# Serial_to_USB_Converter.net
KiCad netlist of a schematic drawn in Altium Designer
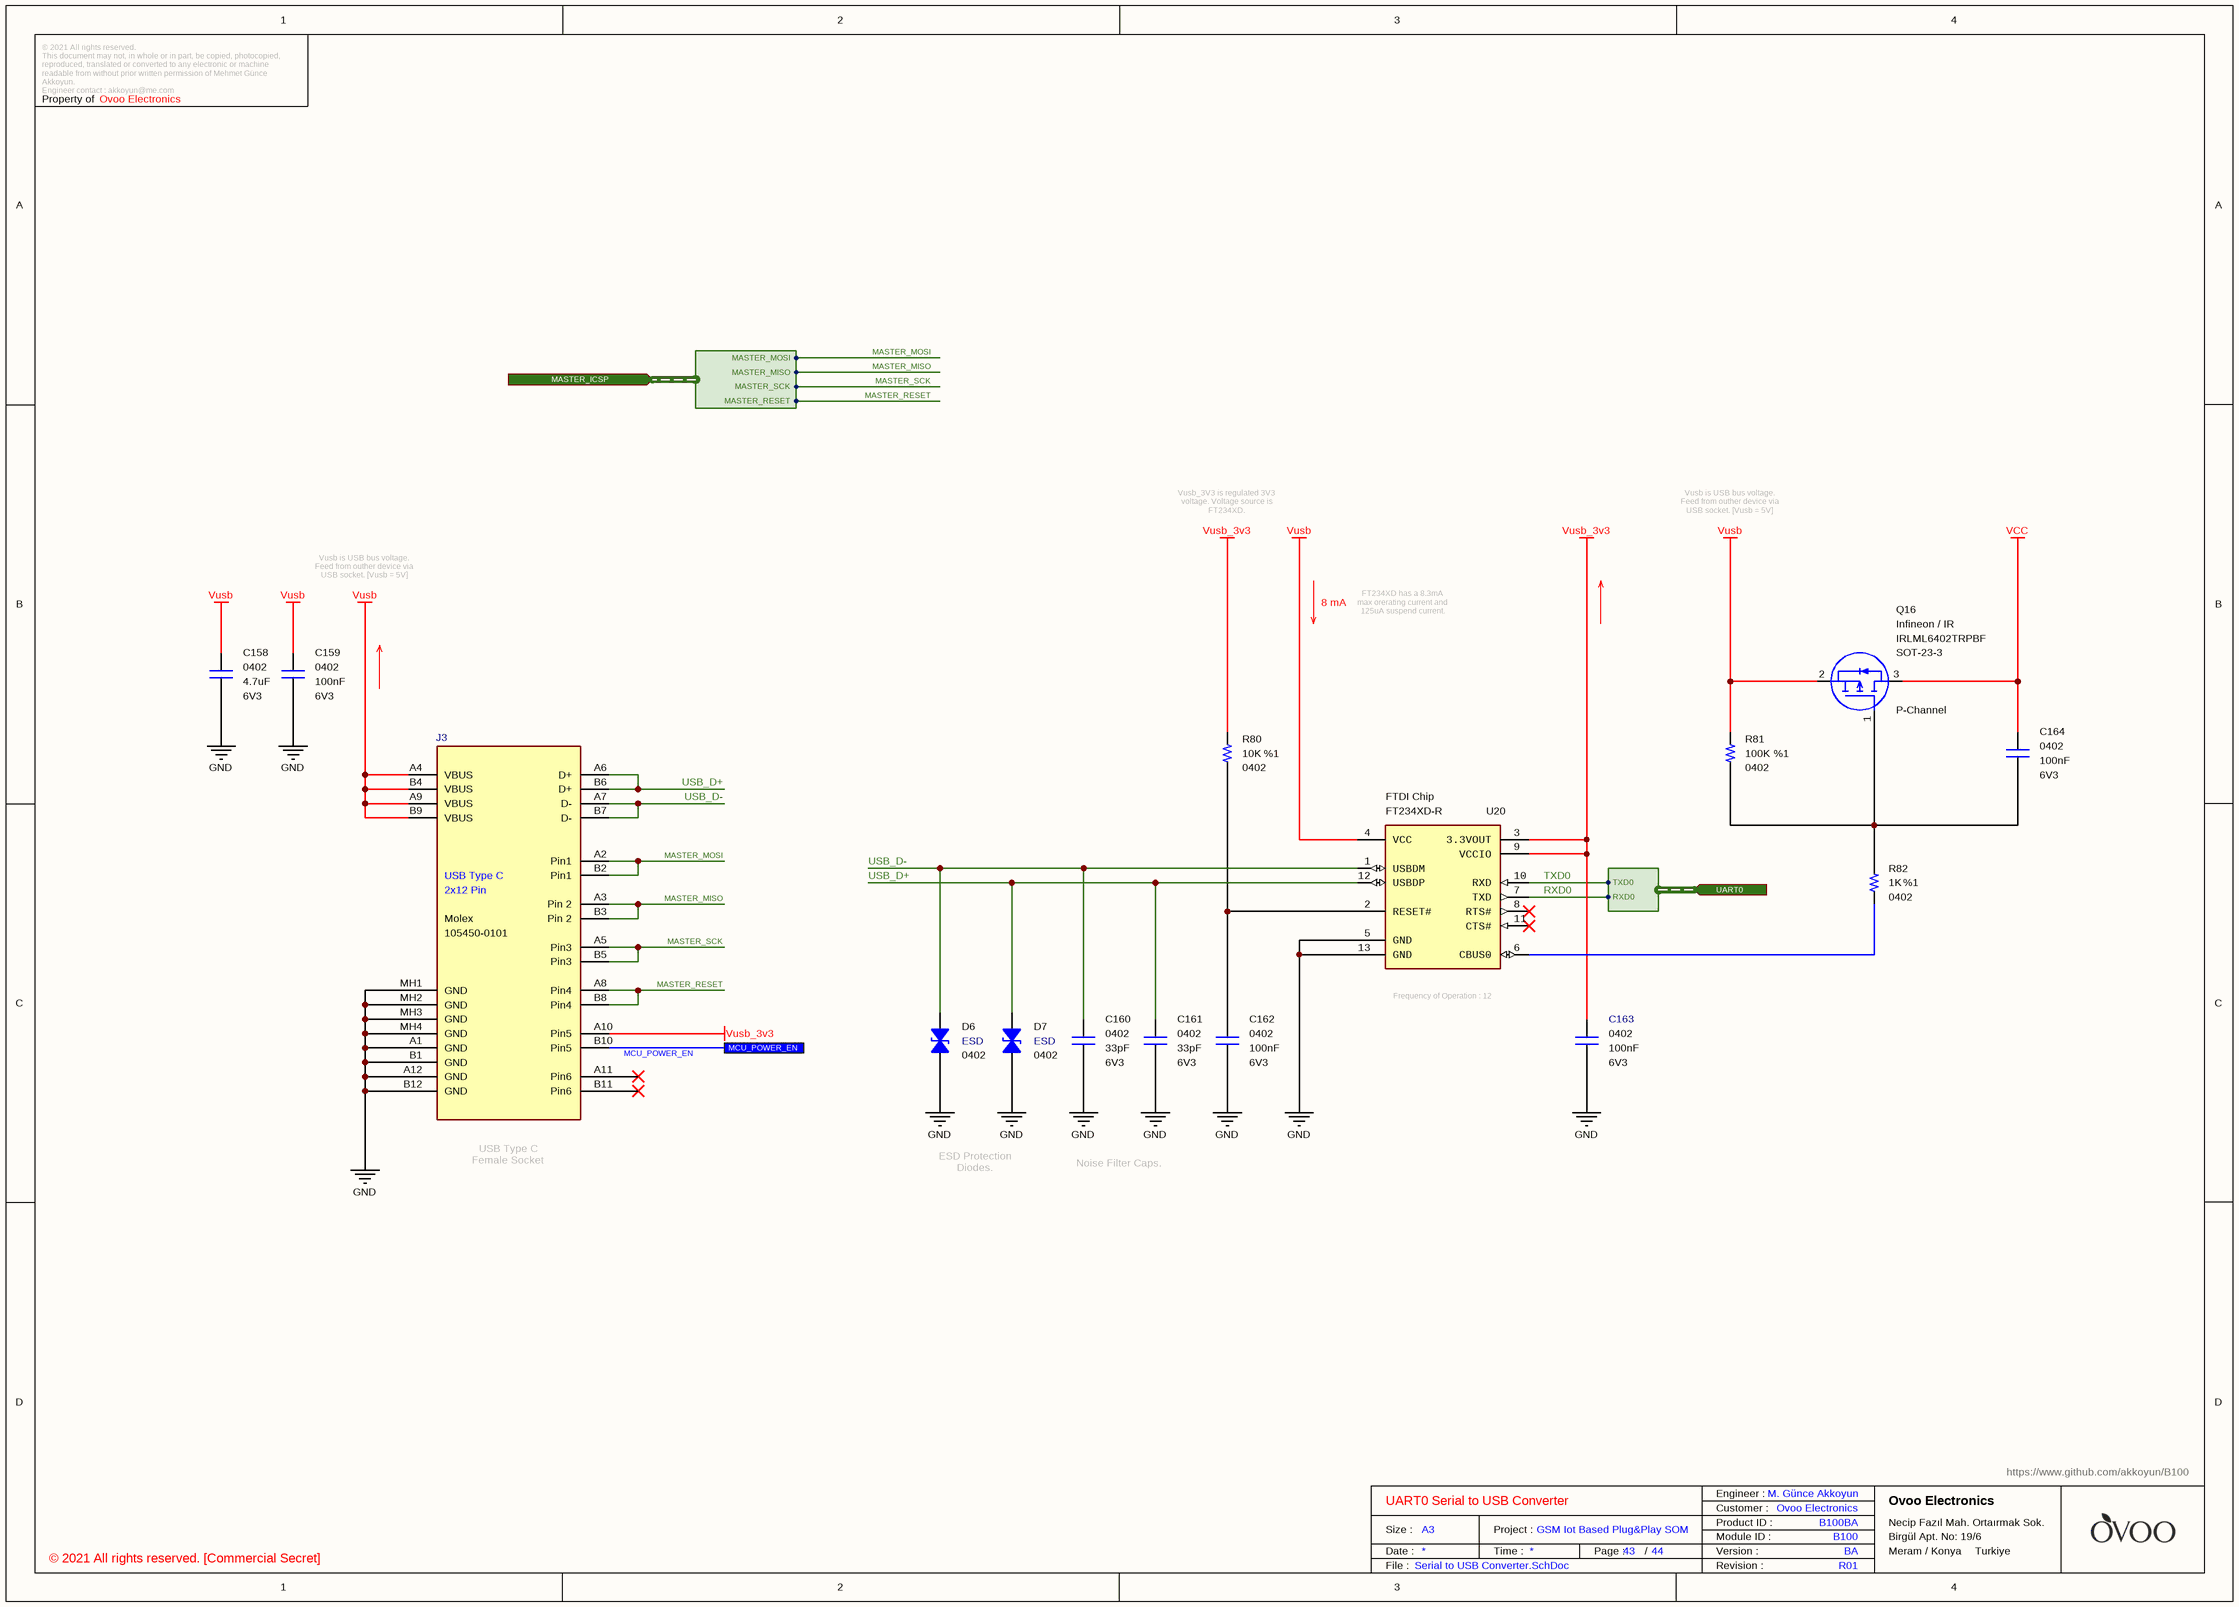
[diagram p0: Serial to USB Converter.SchDoc]

(export (version "E")
  (design (tool "Eeschema 10.0.6"))
  (components
    (comp (ref "C158")
      (value "4.7uF")
      (footprint "CAPACITOR_0402")
      (description "Capacitor - 4.7uF [0402] (Ceramic)")
      (fields
        (field (name "TOLERANCE") "%20")
        (field (name "CASE") "0402")
        (field (name "VOLTAGE") "6V3")
        (field (name "MANUFACTURER PART NUMBER") "C0402C475M9PACTU")
      )
      (libsource (lib "Ovoo_Library") (part "Capacitor - 4.7uF [0402-6V3]"))
    )
    (comp (ref "C159")
      (value "100nF")
      (footprint "CAPACITOR_0402")
      (description "Capacitor - 100nF [0402-6V3] (Ceramic)")
      (fields
        (field (name "TOLERANCE") "%10")
        (field (name "CASE") "0402")
        (field (name "VOLTAGE") "6V3")
        (field (name "MANUFACTURER PART NUMBER") "04026D104KAT4A")
      )
      (libsource (lib "Ovoo_Library") (part "Capacitor - 100nF [0402-6V3]"))
    )
    (comp (ref "C160")
      (value "33pF")
      (footprint "CAPACITOR_0402")
      (description "Capacitor - 33pF [0402] (Ceramic)")
      (fields
        (field (name "TOLERANCE") "10%")
        (field (name "CASE") "0402")
        (field (name "VOLTAGE") "6V3")
        (field (name "MANUFACTURER PART NUMBER") "C0402C330J9RACAUTO")
      )
      (libsource (lib "Ovoo_Library") (part "Capacitor - 33pF [0402-6V3]"))
    )
    (comp (ref "C161")
      (value "33pF")
      (footprint "CAPACITOR_0402")
      (description "Capacitor - 33pF [0402] (Ceramic)")
      (fields
        (field (name "TOLERANCE") "10%")
        (field (name "CASE") "0402")
        (field (name "VOLTAGE") "6V3")
        (field (name "MANUFACTURER PART NUMBER") "C0402C330J9RACAUTO")
      )
      (libsource (lib "Ovoo_Library") (part "Capacitor - 33pF [0402-6V3]"))
    )
    (comp (ref "C162")
      (value "100nF")
      (footprint "CAPACITOR_0402")
      (description "Capacitor - 100nF [0402-6V3] (Ceramic)")
      (fields
        (field (name "CASE") "0402")
        (field (name "TOLERANCE") "%10")
        (field (name "VOLTAGE") "6V3")
        (field (name "MANUFACTURER PART NUMBER") "04026D104KAT4A")
      )
      (libsource (lib "Ovoo_Library") (part "Capacitor - 100nF [0402-6V3]"))
    )
    (comp (ref "C163")
      (value "100nF")
      (footprint "CAPACITOR_0402")
      (description "Capacitor - 100nF [0402-6V3] (Ceramic)")
      (fields
        (field (name "CASE") "0402")
        (field (name "TOLERANCE") "%10")
        (field (name "VOLTAGE") "6V3")
        (field (name "MANUFACTURER PART NUMBER") "04026D104KAT4A")
      )
      (libsource (lib "Ovoo_Library") (part "Capacitor - 100nF [0402-6V3]"))
    )
    (comp (ref "C164")
      (value "100nF")
      (footprint "CAPACITOR_0402")
      (description "Capacitor - 100nF [0402-6V3] (Ceramic)")
      (fields
        (field (name "TOLERANCE") "%10")
        (field (name "CASE") "0402")
        (field (name "VOLTAGE") "6V3")
        (field (name "MANUFACTURER PART NUMBER") "04026D104KAT4A")
      )
      (libsource (lib "Ovoo_Library") (part "Capacitor - 100nF [0402-6V3]"))
    )
    (comp (ref "D6")
      (value "ESD Suppressors")
      (footprint "ESD_0402")
      (description "TVS Diode (Bi-directional)")
      (fields
        (field (name "CASE") "0402")
        (field (name "MANUFACTURER PART NUMBER") "0402ESDA-MLP1")
        (field (name "MOUSER PART NUMBER") "504-0402ESDA-MLP1")
      )
      (libsource (lib "Ovoo_Library") (part "Diode - ESD Protection"))
    )
    (comp (ref "D7")
      (value "ESD Suppressors")
      (footprint "ESD_0402")
      (description "TVS Diode (Bi-directional)")
      (fields
        (field (name "CASE") "0402")
        (field (name "MANUFACTURER PART NUMBER") "0402ESDA-MLP1")
        (field (name "MOUSER PART NUMBER") "504-0402ESDA-MLP1")
      )
      (libsource (lib "Ovoo_Library") (part "Diode - ESD Protection"))
    )
    (comp (ref "J3")
      (value "USB Type C SMD Connector")
      (footprint "USB Type C - Molex 105450-0101")
      (description "USB Connectors USB Type C Recep R/A TOPMNT GLD Flash")
      (fields
        (field (name "MANUFACTURER PART NUMBER") "105450-0101")
        (field (name "MANUFACTURER NAME") "Molex")
        (field (name "CONTACT") "24")
      )
      (libsource (lib "Ovoo_Library") (part "Connector - USB Type C"))
    )
    (comp (ref "Q16")
      (value "P-Channel MosFET")
      (footprint "SOT-23-3")
      (description "MOSFET MOSFT P-Ch -3.7A 65mOhm 8nC Log Lvl")
      (fields
        (field (name "TRANSISTOR POLARITY") "P-Channel")
        (field (name "MANUFACTURER PART NUMBER") "IRLML6402TRPBF")
        (field (name "MANUFACTURER NAME") "Infineon / IR")
        (field (name "CASE") "SOT-23-3")
      )
      (libsource (lib "Ovoo_Library") (part "Transistor - IRLML6402TRPBF"))
    )
    (comp (ref "R80")
      (value "10K")
      (footprint "RESISTOR_0402")
      (description "Thick Film Resistors - SMD 1/16 W 10 Kohms 1%")
      (fields
        (field (name "TOLERANCE") "%1")
        (field (name "CASE") "0402")
        (field (name "MANUFACTURER PART NUMBER") "CRCW040210K0FKED")
        (field (name "MOUSER PART NUMBER") "71-CRCW0402-10K-E3")
      )
      (libsource (lib "Ovoo_Library") (part "Resistor - 10K"))
    )
    (comp (ref "R81")
      (value "100K")
      (footprint "RESISTOR_0402")
      (description "Thick Film Resistors - SMD 1/16 W 100 Kohms 1%")
      (fields
        (field (name "MANUFACTURER PART NUMBER") "CRCW0402100KFKED")
        (field (name "MOUSER PART NUMBER") "71-CRCW0402-100K-E3")
        (field (name "TOLERANCE") "%1")
        (field (name "CASE") "0402")
      )
      (libsource (lib "Ovoo_Library") (part "Resistor - 100K"))
    )
    (comp (ref "R82")
      (value "1K")
      (footprint "RESISTOR_0402")
      (description "Thick Film Resistors - SMD 1/16 W 1.0 Kohms 1%")
      (fields
        (field (name "MANUFACTURER PART NUMBER") "CRCW04021K00FKED")
        (field (name "MOUSER PART NUMBER") "71-CRCW0402-1.0K-E3")
        (field (name "TOLERANCE") "%1")
        (field (name "CASE") "0402")
      )
      (libsource (lib "Ovoo_Library") (part "Resistor - 1K"))
    )
    (comp (ref "U20")
      (value "USB/UART IC")
      (footprint "DFN-12")
      (fields
        (field (name "MOUSER PART NUMBER") "895-FT234XD-R")
        (field (name "MANUFACTURER PART NUMBER") "FT234XD-R")
        (field (name "MANUFACTURER NAME") "FTDI Chip")
      )
      (libsource (lib "Ovoo_Library") (part "IC - FT234XD-R"))
    )
  )
  (nets
    (net (code "3") (name "/MASTER_MISO") (class "Default")
      (node (ref "J3") (pin "A3") (pinfunction "Pin_2_A3") (pintype "passive"))
      (node (ref "J3") (pin "B3") (pinfunction "Pin_2_B3") (pintype "passive"))
    )
    (net (code "4") (name "/MASTER_MOSI") (class "Default")
      (node (ref "J3") (pin "A2") (pinfunction "Pin1_A2") (pintype "passive"))
      (node (ref "J3") (pin "B2") (pinfunction "Pin1_B2") (pintype "passive"))
    )
    (net (code "5") (name "/MASTER_RESET") (class "Default")
      (node (ref "J3") (pin "A8") (pinfunction "Pin4_A8") (pintype "passive"))
      (node (ref "J3") (pin "B8") (pinfunction "Pin4_B8") (pintype "passive"))
    )
    (net (code "6") (name "/MASTER_SCK") (class "Default")
      (node (ref "J3") (pin "A5") (pinfunction "Pin3_A5") (pintype "passive"))
      (node (ref "J3") (pin "B5") (pinfunction "Pin3_B5") (pintype "passive"))
    )
    (net (code "7") (name "/MCU_POWER_EN") (class "Default")
      (node (ref "J3") (pin "B10") (pinfunction "Pin5_B10") (pintype "passive"))
    )
    (net (code "8") (name "/RXD0") (class "Default")
      (node (ref "U20") (pin "7") (pinfunction "TXD_7") (pintype "output"))
    )
    (net (code "9") (name "/TXD0") (class "Default")
      (node (ref "U20") (pin "10") (pinfunction "RXD_10") (pintype "input"))
    )
    (net (code "10") (name "/USB_D+") (class "Default")
      (node (ref "C161") (pin "1") (pinfunction "1_1") (pintype "passive"))
      (node (ref "D7") (pin "2") (pinfunction "2_2") (pintype "passive"))
      (node (ref "J3") (pin "A6") (pinfunction "D+_A6") (pintype "passive"))
      (node (ref "J3") (pin "B6") (pinfunction "D+_B6") (pintype "passive"))
      (node (ref "U20") (pin "12") (pinfunction "USBDP_12") (pintype "bidirectional"))
    )
    (net (code "11") (name "/USB_D-") (class "Default")
      (node (ref "C160") (pin "1") (pinfunction "1_1") (pintype "passive"))
      (node (ref "D6") (pin "2") (pinfunction "2_2") (pintype "passive"))
      (node (ref "J3") (pin "A7") (pinfunction "D-_A7") (pintype "passive"))
      (node (ref "J3") (pin "B7") (pinfunction "D-_B7") (pintype "passive"))
      (node (ref "U20") (pin "1") (pinfunction "USBDM_1") (pintype "bidirectional"))
    )
    (net (code "14") (name "GND") (class "Default")
      (node (ref "C158") (pin "1") (pinfunction "1_1") (pintype "passive"))
      (node (ref "C159") (pin "1") (pinfunction "1_1") (pintype "passive"))
      (node (ref "C160") (pin "2") (pinfunction "2_2") (pintype "passive"))
      (node (ref "C161") (pin "2") (pinfunction "2_2") (pintype "passive"))
      (node (ref "C162") (pin "2") (pinfunction "2_2") (pintype "passive"))
      (node (ref "C163") (pin "2") (pinfunction "2_2") (pintype "passive"))
      (node (ref "D6") (pin "1") (pinfunction "1_1") (pintype "passive"))
      (node (ref "D7") (pin "1") (pinfunction "1_1") (pintype "passive"))
      (node (ref "J3") (pin "A1") (pinfunction "GND_A1") (pintype "passive"))
      (node (ref "J3") (pin "A12") (pinfunction "GND_A12") (pintype "passive"))
      (node (ref "J3") (pin "B1") (pinfunction "GND_B1") (pintype "passive"))
      (node (ref "J3") (pin "B12") (pinfunction "GND_B12") (pintype "passive"))
      (node (ref "J3") (pin "MH1") (pinfunction "GND_MH1") (pintype "passive"))
      (node (ref "J3") (pin "MH2") (pinfunction "GND_MH2") (pintype "passive"))
      (node (ref "J3") (pin "MH3") (pinfunction "GND_MH3") (pintype "passive"))
      (node (ref "J3") (pin "MH4") (pinfunction "GND_MH4") (pintype "passive"))
      (node (ref "U20") (pin "13") (pinfunction "GND_13") (pintype "power_in"))
      (node (ref "U20") (pin "5") (pinfunction "GND_5") (pintype "power_in"))
    )
    (net (code "15") (name "Net-(Q16-G)") (class "Default")
      (node (ref "C164") (pin "1") (pinfunction "1_1") (pintype "passive"))
      (node (ref "Q16") (pin "1") (pinfunction "G_1") (pintype "passive"))
      (node (ref "R81") (pin "1") (pinfunction "1_1") (pintype "passive"))
      (node (ref "R82") (pin "2") (pinfunction "2_2") (pintype "passive"))
    )
    (net (code "16") (name "Net-(U20-CBUS0)") (class "Default")
      (node (ref "R82") (pin "1") (pinfunction "1_1") (pintype "passive"))
      (node (ref "U20") (pin "6") (pinfunction "CBUS0_6") (pintype "bidirectional"))
    )
    (net (code "17") (name "Net-(U20-RESET#)") (class "Default")
      (node (ref "C162") (pin "1") (pinfunction "1_1") (pintype "passive"))
      (node (ref "R80") (pin "1") (pinfunction "1_1") (pintype "passive"))
      (node (ref "U20") (pin "2") (pinfunction "RESET#_2") (pintype "passive"))
    )
    (net (code "18") (name "VCC") (class "Default")
      (node (ref "C164") (pin "2") (pinfunction "2_2") (pintype "passive"))
      (node (ref "Q16") (pin "3") (pinfunction "D_3") (pintype "passive"))
    )
    (net (code "19") (name "Vusb") (class "Default")
      (node (ref "C158") (pin "2") (pinfunction "2_2") (pintype "passive"))
      (node (ref "C159") (pin "2") (pinfunction "2_2") (pintype "passive"))
      (node (ref "J3") (pin "A4") (pinfunction "VBUS_A4") (pintype "passive"))
      (node (ref "J3") (pin "A9") (pinfunction "VBUS_A9") (pintype "passive"))
      (node (ref "J3") (pin "B4") (pinfunction "VBUS_B4") (pintype "passive"))
      (node (ref "J3") (pin "B9") (pinfunction "VBUS_B9") (pintype "passive"))
      (node (ref "Q16") (pin "2") (pinfunction "S_2") (pintype "passive"))
      (node (ref "R81") (pin "2") (pinfunction "2_2") (pintype "passive"))
      (node (ref "U20") (pin "4") (pinfunction "VCC_4") (pintype "power_in"))
    )
    (net (code "20") (name "Vusb_3v3") (class "Default")
      (node (ref "C163") (pin "1") (pinfunction "1_1") (pintype "passive"))
      (node (ref "J3") (pin "A10") (pinfunction "Pin5_A10") (pintype "passive"))
      (node (ref "R80") (pin "2") (pinfunction "2_2") (pintype "passive"))
      (node (ref "U20") (pin "3") (pinfunction "3.3VOUT_3") (pintype "power_in"))
      (node (ref "U20") (pin "9") (pinfunction "VCCIO_9") (pintype "power_in"))
    )
    (net (code "21") (name "unconnected-(J3-Pin6-PadA11)") (class "Default")
      (node (ref "J3") (pin "A11") (pinfunction "Pin6_A11") (pintype "passive+no_connect"))
    )
    (net (code "22") (name "unconnected-(J3-Pin6-PadB11)") (class "Default")
      (node (ref "J3") (pin "B11") (pinfunction "Pin6_B11") (pintype "passive+no_connect"))
    )
    (net (code "23") (name "unconnected-(U20-CTS#-Pad11)") (class "Default")
      (node (ref "U20") (pin "11") (pinfunction "CTS#_11") (pintype "input+no_connect"))
    )
    (net (code "24") (name "unconnected-(U20-RTS#-Pad8)") (class "Default")
      (node (ref "U20") (pin "8") (pinfunction "RTS#_8") (pintype "output+no_connect"))
    )
  )
)
